# dev_style_sim7000a_cell_rev0_1.net
KiCad netlist of a schematic drawn in EAGLE
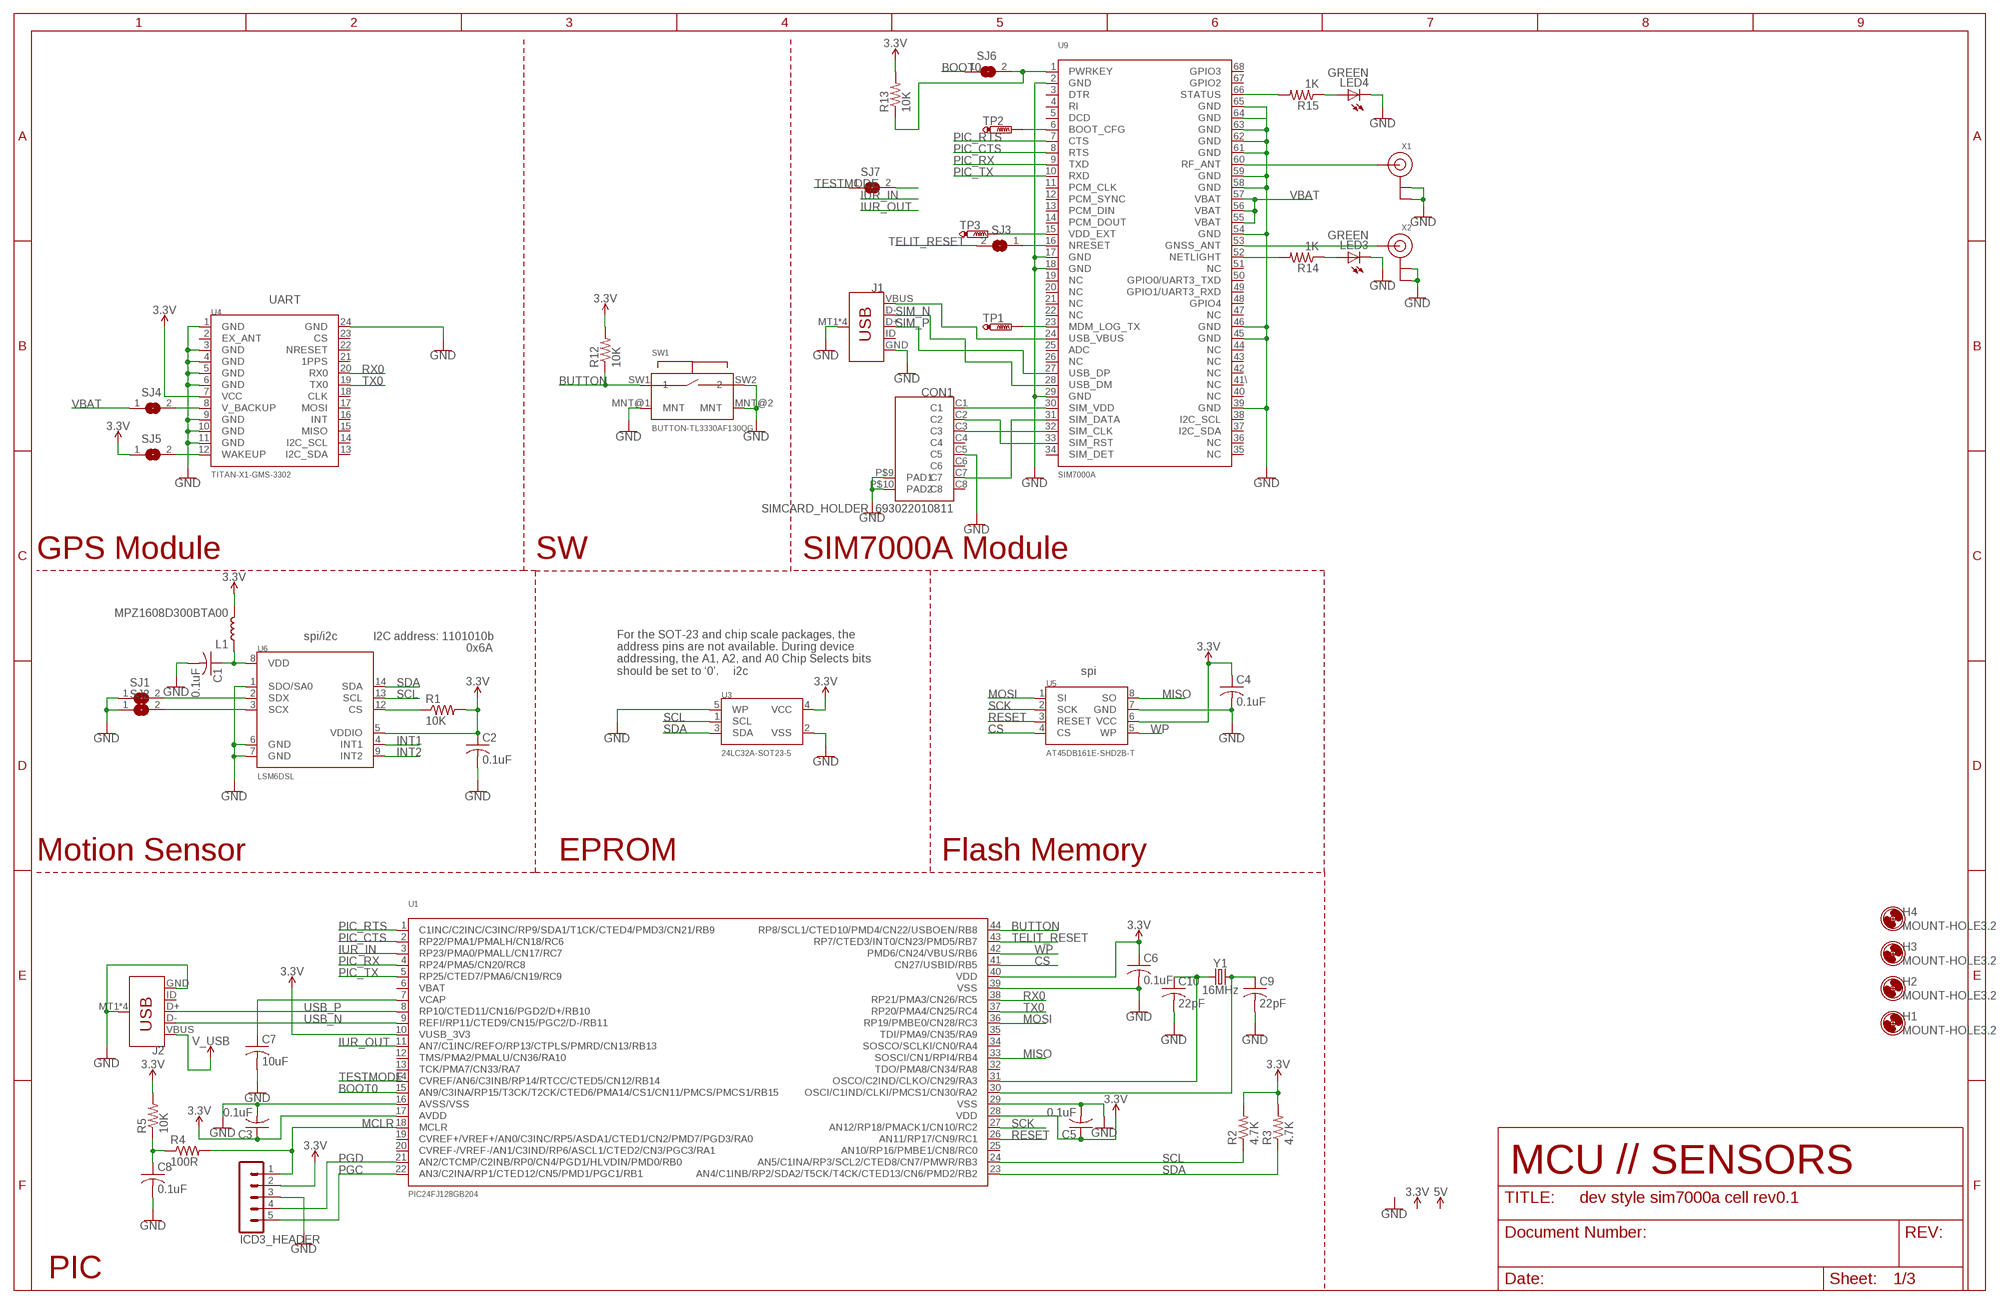
[diagram p0: schematic, sheet 1]
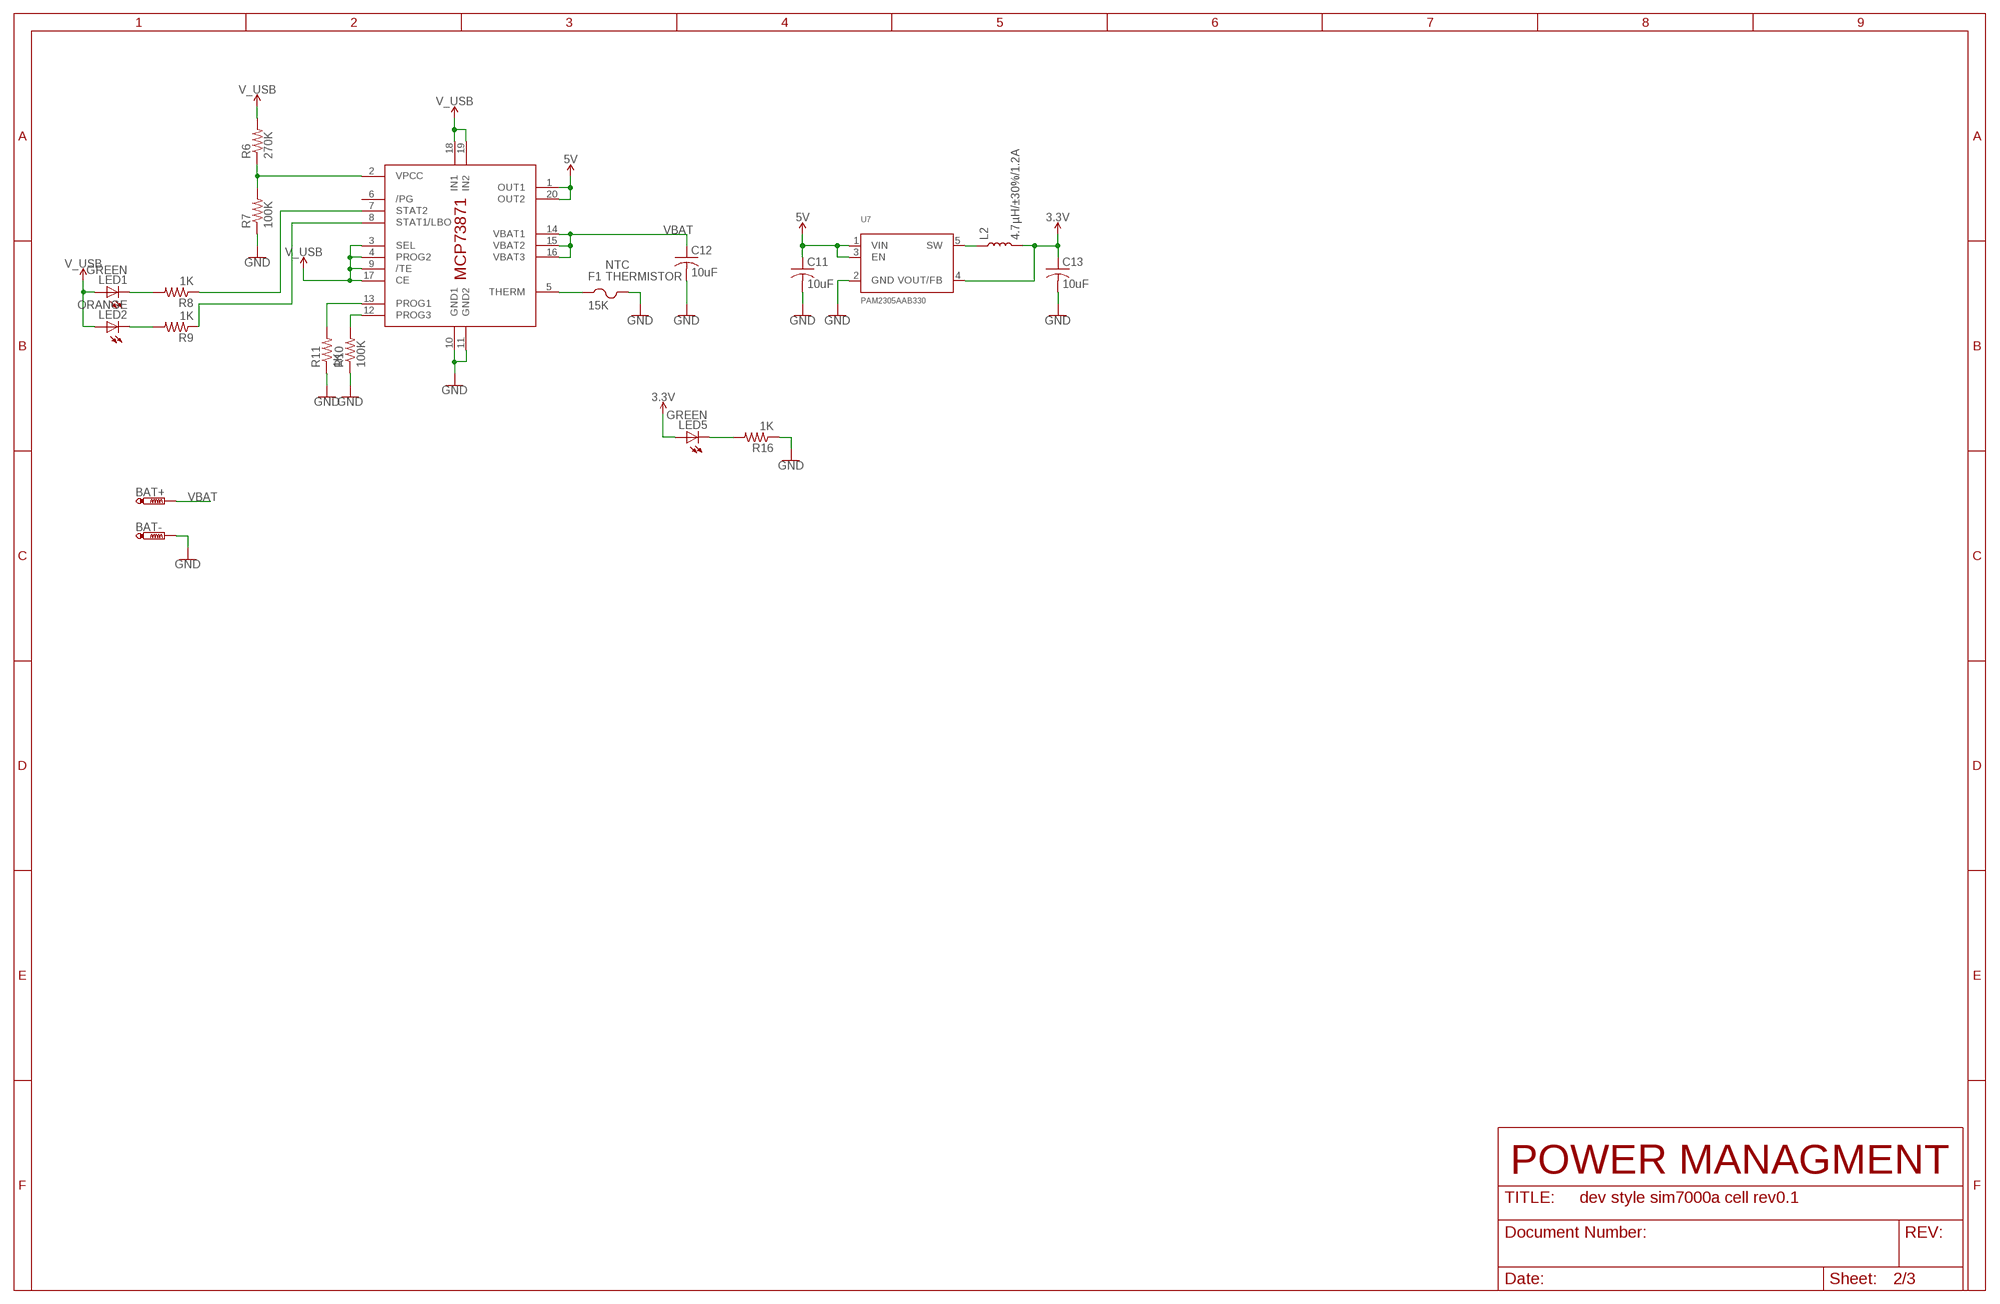
[diagram p1: schematic, sheet 2]
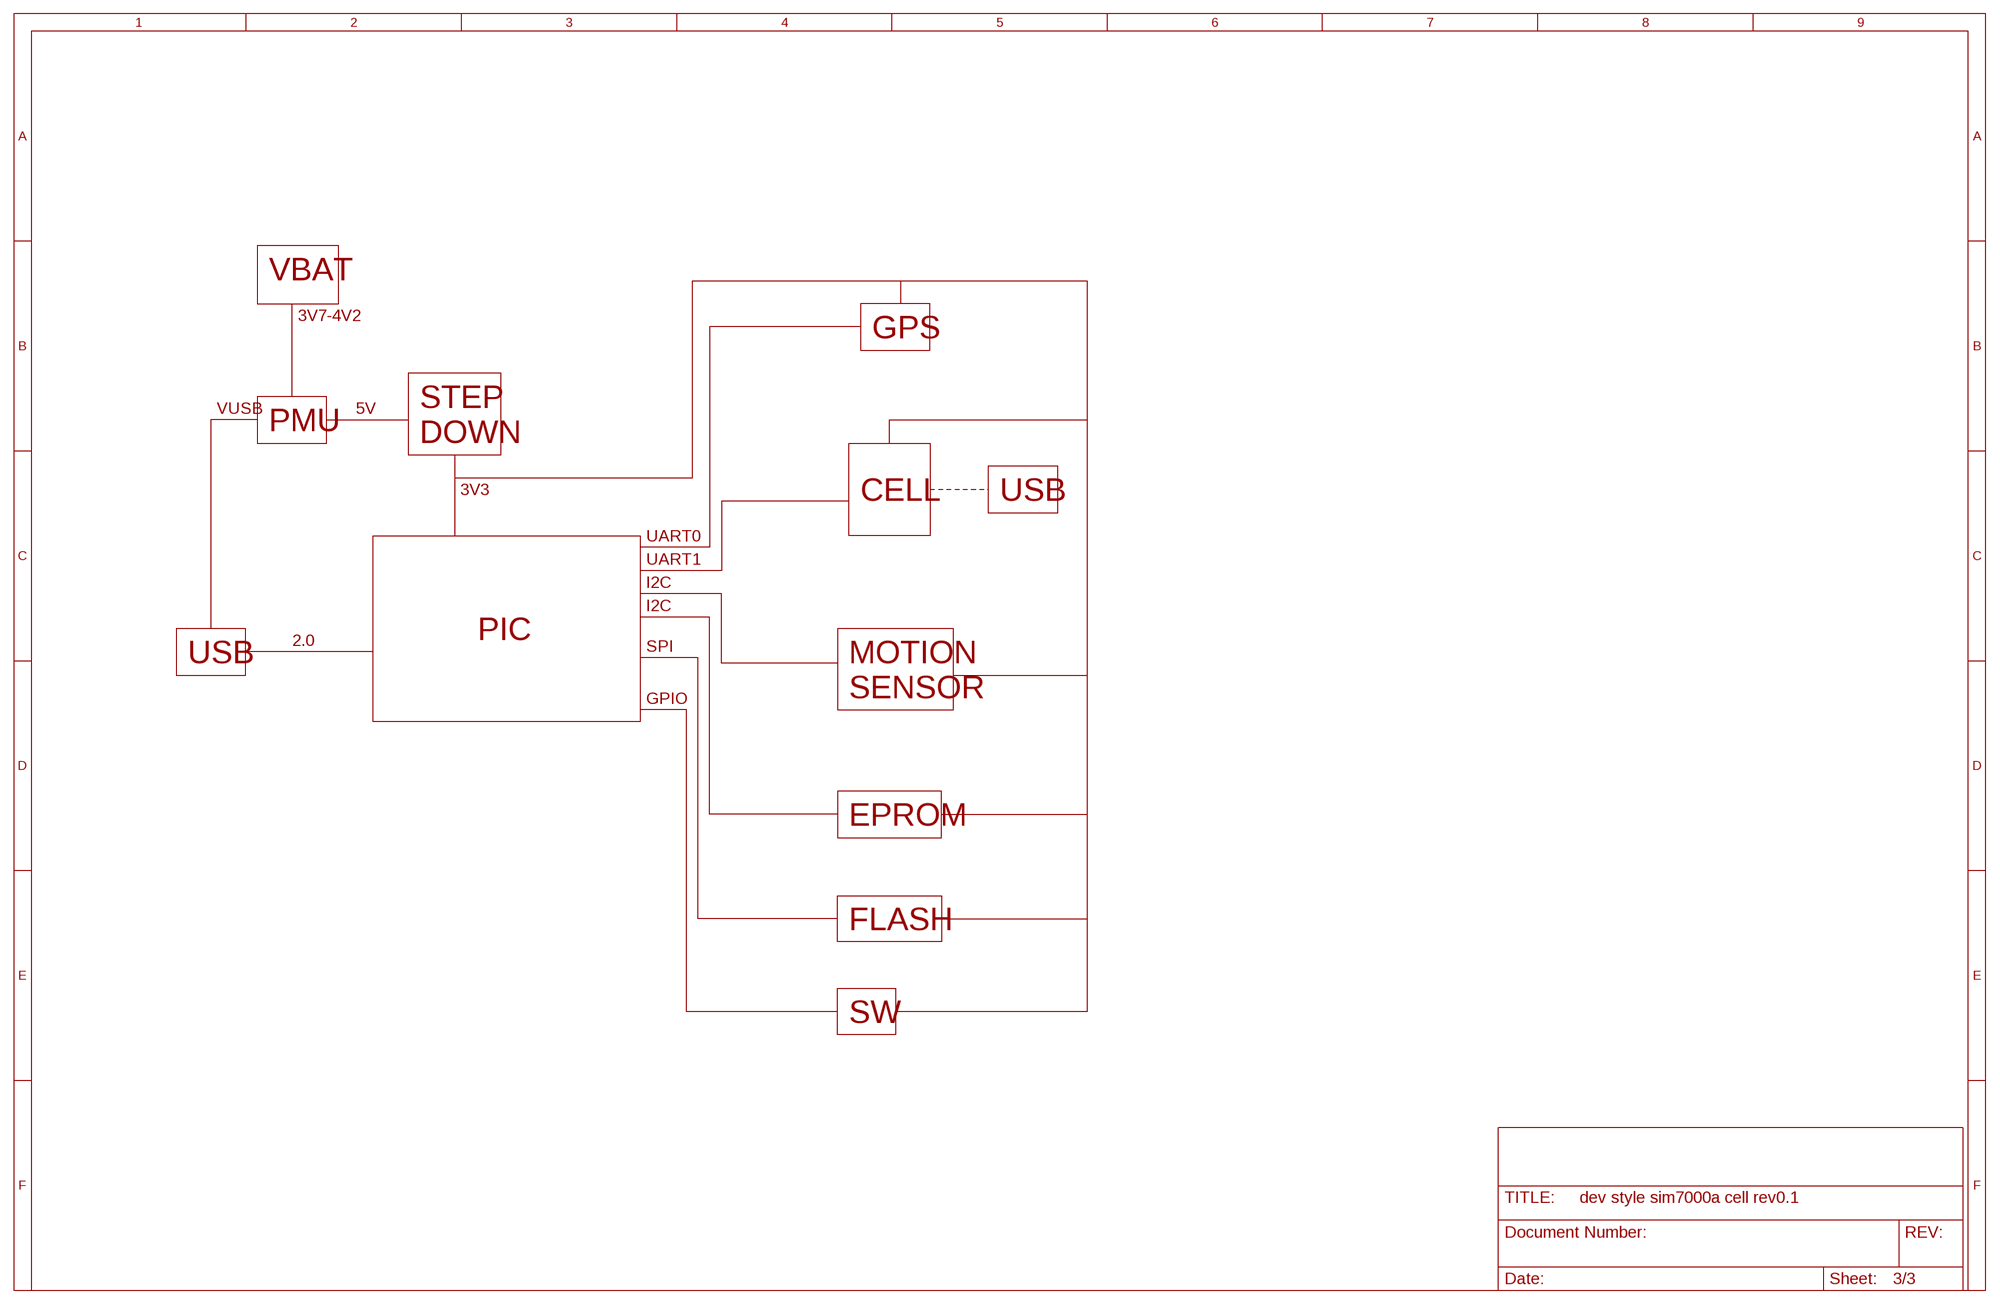
[diagram p2: schematic, sheet 3]

(export (version "E")
  (design (tool "Eeschema 10.0.6"))
  (components
    (comp (ref "C1")
      (value "0.1uF")
      (footprint "eagle-import:C0402")
      (libsource (lib "eagle-import") (part "C-USC0402"))
    )
    (comp (ref "C2")
      (value "0.1uF")
      (footprint "eagle-import:C0402")
      (libsource (lib "eagle-import") (part "C-USC0402"))
    )
    (comp (ref "C3")
      (value "0.1uF")
      (footprint "eagle-import:C0402")
      (libsource (lib "eagle-import") (part "C-USC0402"))
    )
    (comp (ref "C4")
      (value "0.1uF")
      (footprint "eagle-import:C0402")
      (libsource (lib "eagle-import") (part "C-USC0402"))
    )
    (comp (ref "C5")
      (value "0.1uF")
      (footprint "eagle-import:C0402")
      (libsource (lib "eagle-import") (part "C-USC0402"))
    )
    (comp (ref "C6")
      (value "0.1uF")
      (footprint "eagle-import:C0402")
      (libsource (lib "eagle-import") (part "C-USC0402"))
    )
    (comp (ref "C7")
      (value "10uF")
      (footprint "eagle-import:C0603")
      (libsource (lib "eagle-import") (part "C-USC0603"))
    )
    (comp (ref "C8")
      (value "0.1uF")
      (footprint "eagle-import:C0402")
      (libsource (lib "eagle-import") (part "C-USC0402"))
    )
    (comp (ref "C9")
      (value "22pF")
      (footprint "eagle-import:C0402")
      (libsource (lib "eagle-import") (part "C-USC0402"))
    )
    (comp (ref "C10")
      (value "22pF")
      (footprint "eagle-import:C0402")
      (libsource (lib "eagle-import") (part "C-USC0402"))
    )
    (comp (ref "CON1")
      (value "SIMCARD_HOLDER_693022010811")
      (footprint "eagle-import:SIMCARD_HOLDER_693022010811")
      (libsource (lib "eagle-import") (part "SIMCARD_HOLDER_693022010811"))
    )
    (comp (ref "H1")
      (value "MOUNT-HOLE3.2")
      (footprint "eagle-import:3,2")
      (libsource (lib "eagle-import") (part "MOUNT-HOLE3.2"))
    )
    (comp (ref "H2")
      (value "MOUNT-HOLE3.2")
      (footprint "eagle-import:3,2")
      (libsource (lib "eagle-import") (part "MOUNT-HOLE3.2"))
    )
    (comp (ref "H3")
      (value "MOUNT-HOLE3.2")
      (footprint "eagle-import:3,2")
      (libsource (lib "eagle-import") (part "MOUNT-HOLE3.2"))
    )
    (comp (ref "H4")
      (value "MOUNT-HOLE3.2")
      (footprint "eagle-import:3,2")
      (libsource (lib "eagle-import") (part "MOUNT-HOLE3.2"))
    )
    (comp (ref "ICD3_HEADER")
      (value "MA05-1")
      (footprint "eagle-import:MA05-1")
      (libsource (lib "eagle-import") (part "MA05-1"))
    )
    (comp (ref "J1")
      (value "USB_MICRO-B_SMT")
      (footprint "eagle-import:USB-MICROB")
      (libsource (lib "eagle-import") (part "USB_MICRO-B_SMT"))
    )
    (comp (ref "J2")
      (value "USB_MICRO-B_SMT")
      (footprint "eagle-import:USB-MICROB")
      (libsource (lib "eagle-import") (part "USB_MICRO-B_SMT"))
    )
    (comp (ref "L1")
      (value "MPZ1608D300BTA00")
      (footprint "eagle-import:0402")
      (libsource (lib "eagle-import") (part "INDUCTOR-0402-3.9NH"))
    )
    (comp (ref "LED3")
      (value "GREEN")
      (footprint "eagle-import:CHIP-LED0603")
      (libsource (lib "eagle-import") (part "LEDCHIP-LED0603"))
    )
    (comp (ref "LED4")
      (value "GREEN")
      (footprint "eagle-import:CHIP-LED0603")
      (libsource (lib "eagle-import") (part "LEDCHIP-LED0603"))
    )
    (comp (ref "R1")
      (value "10K")
      (footprint "eagle-import:R0402")
      (libsource (lib "eagle-import") (part "R-US_R0402"))
    )
    (comp (ref "R2")
      (value "4.7K")
      (footprint "eagle-import:R0402")
      (libsource (lib "eagle-import") (part "R-US_R0402"))
    )
    (comp (ref "R3")
      (value "4.7K")
      (footprint "eagle-import:R0402")
      (libsource (lib "eagle-import") (part "R-US_R0402"))
    )
    (comp (ref "R4")
      (value "100R")
      (footprint "eagle-import:R0402")
      (libsource (lib "eagle-import") (part "R-US_R0402"))
    )
    (comp (ref "R5")
      (value "10K")
      (footprint "eagle-import:R0402")
      (libsource (lib "eagle-import") (part "R-US_R0402"))
    )
    (comp (ref "R12")
      (value "10K")
      (footprint "eagle-import:R0402")
      (libsource (lib "eagle-import") (part "R-US_R0402"))
    )
    (comp (ref "R13")
      (value "10K")
      (footprint "eagle-import:R0402")
      (libsource (lib "eagle-import") (part "R-US_R0402"))
    )
    (comp (ref "R14")
      (value "1K")
      (footprint "eagle-import:R0402")
      (libsource (lib "eagle-import") (part "R-US_R0402"))
    )
    (comp (ref "R15")
      (value "1K")
      (footprint "eagle-import:R0402")
      (libsource (lib "eagle-import") (part "R-US_R0402"))
    )
    (comp (ref "SJ1") (value "SJ") (footprint "eagle-import:SJ") (libsource (lib "eagle-import") (part "SJ")))
    (comp (ref "SJ2") (value "SJ") (footprint "eagle-import:SJ") (libsource (lib "eagle-import") (part "SJ")))
    (comp (ref "SJ3") (value "SJ") (footprint "eagle-import:SJ") (libsource (lib "eagle-import") (part "SJ")))
    (comp (ref "SJ4") (value "SJ") (footprint "eagle-import:SJ") (libsource (lib "eagle-import") (part "SJ")))
    (comp (ref "SJ5") (value "SJ") (footprint "eagle-import:SJ") (libsource (lib "eagle-import") (part "SJ")))
    (comp (ref "SJ6") (value "SJ") (footprint "eagle-import:SJ") (libsource (lib "eagle-import") (part "SJ")))
    (comp (ref "SJ7") (value "SJ") (footprint "eagle-import:SJ") (libsource (lib "eagle-import") (part "SJ")))
    (comp (ref "SW1")
      (value "BUTTON-TL3330AF130QG")
      (footprint "eagle-import:BUTTON-TL3330AF130QG")
      (libsource (lib "eagle-import") (part "BUTTON-TL3330AF130QG"))
    )
    (comp (ref "TP1")
      (value "PTR1PAD1-17")
      (footprint "eagle-import:P1-17")
      (libsource (lib "eagle-import") (part "PTR1PAD1-17"))
    )
    (comp (ref "TP2")
      (value "PTR1PAD1-17")
      (footprint "eagle-import:P1-17")
      (libsource (lib "eagle-import") (part "PTR1PAD1-17"))
    )
    (comp (ref "TP3")
      (value "PTR1PAD1-17")
      (footprint "eagle-import:P1-17")
      (libsource (lib "eagle-import") (part "PTR1PAD1-17"))
    )
    (comp (ref "U$1")
      (value "FIDUCIAL")
      (footprint "eagle-import:FIDUCIAL_1MM")
      (libsource (lib "eagle-import") (part "FIDUCIAL"))
    )
    (comp (ref "U$2")
      (value "FIDUCIAL")
      (footprint "eagle-import:FIDUCIAL_1MM")
      (libsource (lib "eagle-import") (part "FIDUCIAL"))
    )
    (comp (ref "U$3")
      (value "FIDUCIAL")
      (footprint "eagle-import:FIDUCIAL_1MM")
      (libsource (lib "eagle-import") (part "FIDUCIAL"))
    )
    (comp (ref "U$4")
      (value "FIDUCIAL")
      (footprint "eagle-import:FIDUCIAL_1MM")
      (libsource (lib "eagle-import") (part "FIDUCIAL"))
    )
    (comp (ref "U1")
      (value "PIC24FJ128GB204")
      (footprint "eagle-import:PIC24FJ128GB204")
      (libsource (lib "eagle-import") (part "PIC24FJ128GB204"))
    )
    (comp (ref "U3")
      (value "24LC32A-SOT23-5")
      (footprint "eagle-import:24LC32A-SOT23-5")
      (libsource (lib "eagle-import") (part "24LC32A-SOT23-5"))
    )
    (comp (ref "U4")
      (value "TITAN-X1-GMS-3302")
      (footprint "eagle-import:TITAN-X1-GMS-3302")
      (libsource (lib "eagle-import") (part "TITAN-X1-GMS-3302"))
    )
    (comp (ref "U5")
      (value "AT45DB161E-SHD2B-T")
      (footprint "eagle-import:AT45DB161E-SHD2B-T")
      (libsource (lib "eagle-import") (part "AT45DB161E-SHD2B-T"))
    )
    (comp (ref "U6")
      (value "LSM6DSL")
      (footprint "eagle-import:LSM6DSL")
      (fields (field (name "SPICEPREFIX") "X"))
      (libsource (lib "eagle-import") (part "LSM6DSL"))
    )
    (comp (ref "U9")
      (value "SIM7000A")
      (footprint "eagle-import:SIM7000A")
      (libsource (lib "eagle-import") (part "SIM7000A"))
    )
    (comp (ref "X1")
      (value "ANTENNA_U.FL")
      (footprint "eagle-import:U.FL")
      (libsource (lib "eagle-import") (part "ANTENNA_U.FL"))
    )
    (comp (ref "X2")
      (value "ANTENNA_U.FL")
      (footprint "eagle-import:U.FL")
      (libsource (lib "eagle-import") (part "ANTENNA_U.FL"))
    )
    (comp (ref "Y1")
      (value "16MHz")
      (footprint "eagle-import:CRYSTAL-SMD-5X3.2-4PAD")
      (libsource (lib "eagle-import") (part "CRYSTAL-16MHZSMD-5X3.2"))
    )
    (comp (ref "BAT+")
      (value "PTR1B2,54")
      (footprint "eagle-import:B2,54")
      (libsource (lib "eagle-import") (part "PTR1B2,54"))
    )
    (comp (ref "BAT-")
      (value "PTR1B2,54")
      (footprint "eagle-import:B2,54")
      (libsource (lib "eagle-import") (part "PTR1B2,54"))
    )
    (comp (ref "C11")
      (value "10uF")
      (footprint "eagle-import:C0805")
      (libsource (lib "eagle-import") (part "C-USC0805"))
    )
    (comp (ref "C12")
      (value "10uF")
      (footprint "eagle-import:C0603")
      (libsource (lib "eagle-import") (part "C-USC0603"))
    )
    (comp (ref "C13")
      (value "10uF")
      (footprint "eagle-import:C0805")
      (libsource (lib "eagle-import") (part "C-USC0805"))
    )
    (comp (ref "F1")
      (value "15K")
      (footprint "eagle-import:R1206")
      (libsource (lib "eagle-import") (part "PTCFUSE-1206"))
    )
    (comp (ref "L2")
      (value "4.7µH/±30%/1.2A")
      (footprint "eagle-import:INDUCTOR_4.7UH")
      (libsource (lib "eagle-import") (part "INDUCTOR-CDRH-4.7UH"))
    )
    (comp (ref "LED1")
      (value "GREEN")
      (footprint "eagle-import:CHIP-LED0603")
      (libsource (lib "eagle-import") (part "LEDCHIP-LED0603"))
    )
    (comp (ref "LED2")
      (value "ORANGE")
      (footprint "eagle-import:CHIP-LED0603")
      (libsource (lib "eagle-import") (part "LEDCHIP-LED0603"))
    )
    (comp (ref "LED5")
      (value "GREEN")
      (footprint "eagle-import:CHIP-LED0603")
      (libsource (lib "eagle-import") (part "LEDCHIP-LED0603"))
    )
    (comp (ref "R6")
      (value "270K")
      (footprint "eagle-import:R0402")
      (libsource (lib "eagle-import") (part "R-US_R0402"))
    )
    (comp (ref "R7")
      (value "100K")
      (footprint "eagle-import:R0402")
      (libsource (lib "eagle-import") (part "R-US_R0402"))
    )
    (comp (ref "R8")
      (value "1K")
      (footprint "eagle-import:R0402")
      (libsource (lib "eagle-import") (part "R-US_R0402"))
    )
    (comp (ref "R9")
      (value "1K")
      (footprint "eagle-import:R0402")
      (libsource (lib "eagle-import") (part "R-US_R0402"))
    )
    (comp (ref "R10")
      (value "100K")
      (footprint "eagle-import:R0402")
      (libsource (lib "eagle-import") (part "R-US_R0402"))
    )
    (comp (ref "R11")
      (value "1K")
      (footprint "eagle-import:R0402")
      (libsource (lib "eagle-import") (part "R-US_R0402"))
    )
    (comp (ref "R16")
      (value "1K")
      (footprint "eagle-import:R0402")
      (libsource (lib "eagle-import") (part "R-US_R0402"))
    )
    (comp (ref "U7")
      (value "PAM2305AAB330")
      (footprint "eagle-import:PAM2305AAB330")
      (libsource (lib "eagle-import") (part "PAM2305AAB330"))
    )
    (comp (ref "U8")
      (value "MCP73871")
      (footprint "eagle-import:QFN20")
      (libsource (lib "eagle-import") (part "MCP73871"))
    )
  )
  (nets
    (net (code "1") (name "3.3V") (class "Default")
      (node (ref "C13") (pin "1") (pinfunction "1_1") (pintype "passive"))
      (node (ref "C2") (pin "1") (pinfunction "1_1") (pintype "passive"))
      (node (ref "C3") (pin "1") (pinfunction "1_1") (pintype "passive"))
      (node (ref "C4") (pin "1") (pinfunction "1_1") (pintype "passive"))
      (node (ref "C5") (pin "1") (pinfunction "1_1") (pintype "passive"))
      (node (ref "C6") (pin "1") (pinfunction "1_1") (pintype "passive"))
      (node (ref "ICD3_HEADER") (pin "2") (pinfunction "2_2") (pintype "passive"))
      (node (ref "L1") (pin "2") (pinfunction "2_2") (pintype "passive"))
      (node (ref "L2") (pin "P$2") (pinfunction "2_P$2") (pintype "passive"))
      (node (ref "LED5") (pin "A") (pinfunction "A_A") (pintype "passive"))
      (node (ref "R1") (pin "2") (pinfunction "2_2") (pintype "passive"))
      (node (ref "R12") (pin "2") (pinfunction "2_2") (pintype "passive"))
      (node (ref "R13") (pin "2") (pinfunction "2_2") (pintype "passive"))
      (node (ref "R2") (pin "2") (pinfunction "2_2") (pintype "passive"))
      (node (ref "R3") (pin "2") (pinfunction "2_2") (pintype "passive"))
      (node (ref "R5") (pin "2") (pinfunction "2_2") (pintype "passive"))
      (node (ref "SJ5") (pin "1") (pinfunction "1_1") (pintype "passive"))
      (node (ref "U1") (pin "10") (pinfunction "VUSB_3V3_10") (pintype "bidirectional"))
      (node (ref "U1") (pin "17") (pinfunction "AVDD_17") (pintype "bidirectional"))
      (node (ref "U1") (pin "28") (pinfunction "VDD_28") (pintype "bidirectional"))
      (node (ref "U1") (pin "40") (pinfunction "VDD_40") (pintype "bidirectional"))
      (node (ref "U3") (pin "4") (pinfunction "VCC_4") (pintype "bidirectional"))
      (node (ref "U4") (pin "7") (pinfunction "VCC_7") (pintype "bidirectional"))
      (node (ref "U5") (pin "6") (pinfunction "VCC_6") (pintype "bidirectional"))
      (node (ref "U6") (pin "5") (pinfunction "VDDIO_5") (pintype "bidirectional"))
      (node (ref "U7") (pin "4") (pinfunction "VOUT/FB_4") (pintype "bidirectional"))
    )
    (net (code "2") (name "5V") (class "Default")
      (node (ref "C11") (pin "1") (pinfunction "1_1") (pintype "passive"))
      (node (ref "U7") (pin "1") (pinfunction "VIN_1") (pintype "bidirectional"))
      (node (ref "U7") (pin "3") (pinfunction "EN_3") (pintype "bidirectional"))
      (node (ref "U8") (pin "1") (pinfunction "OUT1_1") (pintype "output"))
      (node (ref "U8") (pin "20") (pinfunction "OUT2_20") (pintype "output"))
    )
    (net (code "3") (name "BOOT0") (class "Default")
      (node (ref "SJ6") (pin "1") (pinfunction "1_1") (pintype "passive"))
      (node (ref "U1") (pin "15") (pinfunction "AN9/C3INA/RP15/T3CK/T2CK/CTED6/PMA14/CS1/CN11/PMCS/PMCS1/RB15_15") (pintype "bidirectional"))
    )
    (net (code "4") (name "BUTTON") (class "Default")
      (node (ref "R12") (pin "1") (pinfunction "1_1") (pintype "passive"))
      (node (ref "SW1") (pin "SW1") (pinfunction "1_SW1") (pintype "bidirectional"))
      (node (ref "U1") (pin "44") (pinfunction "RP8/SCL1/CTED10/PMD4/CN22/USBOEN/RB8_44") (pintype "bidirectional"))
    )
    (net (code "5") (name "CS") (class "Default")
      (node (ref "U1") (pin "41") (pinfunction "CN27/USBID/RB5_41") (pintype "bidirectional"))
      (node (ref "U5") (pin "4") (pinfunction "CS_4") (pintype "bidirectional"))
    )
    (net (code "6") (name "GND") (class "Default")
      (node (ref "BAT-") (pin "TP") (pinfunction "TP_TP") (pintype "input"))
      (node (ref "C1") (pin "2") (pinfunction "2_2") (pintype "passive"))
      (node (ref "C10") (pin "2") (pinfunction "2_2") (pintype "passive"))
      (node (ref "C11") (pin "2") (pinfunction "2_2") (pintype "passive"))
      (node (ref "C12") (pin "2") (pinfunction "2_2") (pintype "passive"))
      (node (ref "C13") (pin "2") (pinfunction "2_2") (pintype "passive"))
      (node (ref "C2") (pin "2") (pinfunction "2_2") (pintype "passive"))
      (node (ref "C3") (pin "2") (pinfunction "2_2") (pintype "passive"))
      (node (ref "C4") (pin "2") (pinfunction "2_2") (pintype "passive"))
      (node (ref "C5") (pin "2") (pinfunction "2_2") (pintype "passive"))
      (node (ref "C6") (pin "2") (pinfunction "2_2") (pintype "passive"))
      (node (ref "C7") (pin "2") (pinfunction "2_2") (pintype "passive"))
      (node (ref "C8") (pin "2") (pinfunction "2_2") (pintype "passive"))
      (node (ref "C9") (pin "2") (pinfunction "2_2") (pintype "passive"))
      (node (ref "CON1") (pin "C5") (pinfunction "C5_C5") (pintype "bidirectional"))
      (node (ref "CON1") (pin "P$10") (pinfunction "PAD2_P$10") (pintype "bidirectional"))
      (node (ref "CON1") (pin "P$9") (pinfunction "PAD1_P$9") (pintype "bidirectional"))
      (node (ref "F1") (pin "2") (pinfunction "2_2") (pintype "passive"))
      (node (ref "ICD3_HEADER") (pin "3") (pinfunction "3_3") (pintype "passive"))
      (node (ref "J1") (pin "GND") (pinfunction "GND_GND") (pintype "power_in"))
      (node (ref "J1") (pin "MT1") (pinfunction "SHIELD_MT1") (pintype "bidirectional"))
      (node (ref "J1") (pin "MT2") (pinfunction "SHIELD_MT2") (pintype "bidirectional"))
      (node (ref "J1") (pin "P$1") (pinfunction "SHIELD_P$1") (pintype "bidirectional"))
      (node (ref "J1") (pin "P$2") (pinfunction "SHIELD_P$2") (pintype "bidirectional"))
      (node (ref "J2") (pin "GND") (pinfunction "GND_GND") (pintype "power_in"))
      (node (ref "J2") (pin "MT1") (pinfunction "SHIELD_MT1") (pintype "bidirectional"))
      (node (ref "J2") (pin "MT2") (pinfunction "SHIELD_MT2") (pintype "bidirectional"))
      (node (ref "J2") (pin "P$1") (pinfunction "SHIELD_P$1") (pintype "bidirectional"))
      (node (ref "J2") (pin "P$2") (pinfunction "SHIELD_P$2") (pintype "bidirectional"))
      (node (ref "LED3") (pin "C") (pinfunction "C_C") (pintype "passive"))
      (node (ref "LED4") (pin "C") (pinfunction "C_C") (pintype "passive"))
      (node (ref "R10") (pin "1") (pinfunction "1_1") (pintype "passive"))
      (node (ref "R11") (pin "1") (pinfunction "1_1") (pintype "passive"))
      (node (ref "R16") (pin "1") (pinfunction "1_1") (pintype "passive"))
      (node (ref "R7") (pin "1") (pinfunction "1_1") (pintype "passive"))
      (node (ref "SJ1") (pin "1") (pinfunction "1_1") (pintype "passive"))
      (node (ref "SJ2") (pin "1") (pinfunction "1_1") (pintype "passive"))
      (node (ref "SW1") (pin "MNT@1") (pinfunction "MNT_MNT@1") (pintype "bidirectional"))
      (node (ref "SW1") (pin "MNT@2") (pinfunction "MNT_MNT@2") (pintype "bidirectional"))
      (node (ref "SW1") (pin "SW2") (pinfunction "2_SW2") (pintype "bidirectional"))
      (node (ref "U1") (pin "16") (pinfunction "AVSS/VSS_16") (pintype "bidirectional"))
      (node (ref "U1") (pin "29") (pinfunction "VSS_29") (pintype "bidirectional"))
      (node (ref "U1") (pin "39") (pinfunction "VSS_39") (pintype "bidirectional"))
      (node (ref "U3") (pin "2") (pinfunction "VSS_2") (pintype "bidirectional"))
      (node (ref "U3") (pin "5") (pinfunction "WP_5") (pintype "bidirectional"))
      (node (ref "U4") (pin "1") (pinfunction "GND_1") (pintype "bidirectional"))
      (node (ref "U4") (pin "10") (pinfunction "GND_10") (pintype "bidirectional"))
      (node (ref "U4") (pin "11") (pinfunction "GND_11") (pintype "bidirectional"))
      (node (ref "U4") (pin "24") (pinfunction "GND_24") (pintype "bidirectional"))
      (node (ref "U4") (pin "3") (pinfunction "GND_3") (pintype "bidirectional"))
      (node (ref "U4") (pin "4") (pinfunction "GND_4") (pintype "bidirectional"))
      (node (ref "U4") (pin "5") (pinfunction "GND_5") (pintype "bidirectional"))
      (node (ref "U4") (pin "6") (pinfunction "GND_6") (pintype "bidirectional"))
      (node (ref "U4") (pin "9") (pinfunction "GND_9") (pintype "bidirectional"))
      (node (ref "U5") (pin "7") (pinfunction "GND_7") (pintype "bidirectional"))
      (node (ref "U6") (pin "1") (pinfunction "SDO/SA0_1") (pintype "bidirectional"))
      (node (ref "U6") (pin "6") (pinfunction "GND_6") (pintype "bidirectional"))
      (node (ref "U6") (pin "7") (pinfunction "GND_7") (pintype "bidirectional"))
      (node (ref "U7") (pin "2") (pinfunction "GND_2") (pintype "bidirectional"))
      (node (ref "U8") (pin "10") (pinfunction "GND1_10") (pintype "power_in"))
      (node (ref "U8") (pin "11") (pinfunction "GND2_11") (pintype "power_in"))
      (node (ref "U9") (pin "17") (pinfunction "GND_17") (pintype "power_in"))
      (node (ref "U9") (pin "18") (pinfunction "GND_18") (pintype "power_in"))
      (node (ref "U9") (pin "2") (pinfunction "GND_2") (pintype "power_in"))
      (node (ref "U9") (pin "29") (pinfunction "GND_29") (pintype "power_in"))
      (node (ref "U9") (pin "39") (pinfunction "GND_39") (pintype "power_in"))
      (node (ref "U9") (pin "45") (pinfunction "GND_45") (pintype "power_in"))
      (node (ref "U9") (pin "46") (pinfunction "GND_46") (pintype "power_in"))
      (node (ref "U9") (pin "54") (pinfunction "GND_54") (pintype "power_in"))
      (node (ref "U9") (pin "58") (pinfunction "GND_58") (pintype "power_in"))
      (node (ref "U9") (pin "59") (pinfunction "GND_59") (pintype "power_in"))
      (node (ref "U9") (pin "61") (pinfunction "GND_61") (pintype "power_in"))
      (node (ref "U9") (pin "62") (pinfunction "GND_62") (pintype "power_in"))
      (node (ref "U9") (pin "63") (pinfunction "GND_63") (pintype "power_in"))
      (node (ref "U9") (pin "64") (pinfunction "GND_64") (pintype "power_in"))
      (node (ref "U9") (pin "65") (pinfunction "GND_65") (pintype "power_in"))
      (node (ref "X1") (pin "1") (pinfunction "GND_1") (pintype "passive"))
      (node (ref "X1") (pin "2") (pinfunction "GND_2") (pintype "passive"))
      (node (ref "X2") (pin "1") (pinfunction "GND_1") (pintype "passive"))
      (node (ref "X2") (pin "2") (pinfunction "GND_2") (pintype "passive"))
    )
    (net (code "7") (name "INT1") (class "Default")
      (node (ref "U6") (pin "4") (pinfunction "INT1_4") (pintype "bidirectional"))
    )
    (net (code "8") (name "INT2") (class "Default")
      (node (ref "U6") (pin "9") (pinfunction "INT2_9") (pintype "bidirectional"))
    )
    (net (code "9") (name "IUR_IN") (class "Default")
      (node (ref "U1") (pin "3") (pinfunction "RP23/PMA0/PMALL/CN17/RC7_3") (pintype "bidirectional"))
    )
    (net (code "10") (name "IUR_OUT") (class "Default")
      (node (ref "U1") (pin "11") (pinfunction "AN7/C1INC/REFO/RP13/CTPLS/PMRD/CN13/RB13_11") (pintype "bidirectional"))
    )
    (net (code "11") (name "MCLR") (class "Default")
      (node (ref "ICD3_HEADER") (pin "1") (pinfunction "1_1") (pintype "passive"))
      (node (ref "R4") (pin "2") (pinfunction "2_2") (pintype "passive"))
      (node (ref "U1") (pin "18") (pinfunction "MCLR_18") (pintype "bidirectional"))
    )
    (net (code "12") (name "MISO") (class "Default")
      (node (ref "U1") (pin "33") (pinfunction "SOSCI/CN1/RPI4/RB4_33") (pintype "bidirectional"))
      (node (ref "U5") (pin "8") (pinfunction "SO_8") (pintype "bidirectional"))
    )
    (net (code "13") (name "MOSI") (class "Default")
      (node (ref "U1") (pin "36") (pinfunction "RP19/PMBE0/CN28/RC3_36") (pintype "bidirectional"))
      (node (ref "U5") (pin "1") (pinfunction "SI_1") (pintype "bidirectional"))
    )
    (net (code "14") (name "Net-(C8-Pad1)") (class "Default")
      (node (ref "C8") (pin "1") (pinfunction "1_1") (pintype "passive"))
      (node (ref "R4") (pin "1") (pinfunction "1_1") (pintype "passive"))
      (node (ref "R5") (pin "1") (pinfunction "1_1") (pintype "passive"))
    )
    (net (code "15") (name "Net-(L2-1)") (class "Default")
      (node (ref "L2") (pin "P$1") (pinfunction "1_P$1") (pintype "passive"))
      (node (ref "U7") (pin "5") (pinfunction "SW_5") (pintype "bidirectional"))
    )
    (net (code "16") (name "Net-(LED1-PadC)") (class "Default")
      (node (ref "LED1") (pin "C") (pinfunction "C_C") (pintype "passive"))
      (node (ref "R8") (pin "2") (pinfunction "2_2") (pintype "passive"))
    )
    (net (code "17") (name "Net-(LED2-PadC)") (class "Default")
      (node (ref "LED2") (pin "C") (pinfunction "C_C") (pintype "passive"))
      (node (ref "R9") (pin "2") (pinfunction "2_2") (pintype "passive"))
    )
    (net (code "18") (name "Net-(LED3-PadA)") (class "Default")
      (node (ref "LED3") (pin "A") (pinfunction "A_A") (pintype "passive"))
      (node (ref "R14") (pin "1") (pinfunction "1_1") (pintype "passive"))
    )
    (net (code "19") (name "Net-(LED4-PadA)") (class "Default")
      (node (ref "LED4") (pin "A") (pinfunction "A_A") (pintype "passive"))
      (node (ref "R15") (pin "1") (pinfunction "1_1") (pintype "passive"))
    )
    (net (code "20") (name "Net-(LED5-PadC)") (class "Default")
      (node (ref "LED5") (pin "C") (pinfunction "C_C") (pintype "passive"))
      (node (ref "R16") (pin "2") (pinfunction "2_2") (pintype "passive"))
    )
    (net (code "21") (name "Net-(U1-OSCI{slash}C1IND{slash}CLKI{slash}PMCS1{slash}CN30{slash}RA2)") (class "Default")
      (node (ref "C9") (pin "1") (pinfunction "1_1") (pintype "passive"))
      (node (ref "U1") (pin "30") (pinfunction "OSCI/C1IND/CLKI/PMCS1/CN30/RA2_30") (pintype "bidirectional"))
      (node (ref "Y1") (pin "3") (pinfunction "2_3") (pintype "passive"))
    )
    (net (code "22") (name "Net-(U1-OSCO{slash}C2IND{slash}CLKO{slash}CN29{slash}RA3)") (class "Default")
      (node (ref "C10") (pin "1") (pinfunction "1_1") (pintype "passive"))
      (node (ref "U1") (pin "31") (pinfunction "OSCO/C2IND/CLKO/CN29/RA3_31") (pintype "bidirectional"))
      (node (ref "Y1") (pin "1") (pinfunction "1_1") (pintype "passive"))
    )
    (net (code "23") (name "Net-(U1-VCAP)") (class "Default")
      (node (ref "C7") (pin "1") (pinfunction "1_1") (pintype "passive"))
      (node (ref "U1") (pin "7") (pinfunction "VCAP_7") (pintype "bidirectional"))
    )
    (net (code "24") (name "Net-(U4-V_BACKUP)") (class "Default")
      (node (ref "SJ4") (pin "2") (pinfunction "2_2") (pintype "passive"))
      (node (ref "U4") (pin "8") (pinfunction "V_BACKUP_8") (pintype "bidirectional"))
    )
    (net (code "25") (name "Net-(U4-WAKEUP)") (class "Default")
      (node (ref "SJ5") (pin "2") (pinfunction "2_2") (pintype "passive"))
      (node (ref "U4") (pin "12") (pinfunction "WAKEUP_12") (pintype "bidirectional"))
    )
    (net (code "26") (name "Net-(U6-CS)") (class "Default")
      (node (ref "R1") (pin "1") (pinfunction "1_1") (pintype "passive"))
      (node (ref "U6") (pin "12") (pinfunction "CS_12") (pintype "bidirectional"))
    )
    (net (code "27") (name "Net-(U6-SCX)") (class "Default")
      (node (ref "SJ2") (pin "2") (pinfunction "2_2") (pintype "passive"))
      (node (ref "U6") (pin "3") (pinfunction "SCX_3") (pintype "bidirectional"))
    )
    (net (code "28") (name "Net-(U6-SDX)") (class "Default")
      (node (ref "SJ1") (pin "2") (pinfunction "2_2") (pintype "passive"))
      (node (ref "U6") (pin "2") (pinfunction "SDX_2") (pintype "bidirectional"))
    )
    (net (code "29") (name "Net-(U6-VDD)") (class "Default")
      (node (ref "C1") (pin "1") (pinfunction "1_1") (pintype "passive"))
      (node (ref "L1") (pin "1") (pinfunction "1_1") (pintype "passive"))
      (node (ref "U6") (pin "8") (pinfunction "VDD_8") (pintype "bidirectional"))
    )
    (net (code "30") (name "Net-(U8-PROG1)") (class "Default")
      (node (ref "R11") (pin "2") (pinfunction "2_2") (pintype "passive"))
      (node (ref "U8") (pin "13") (pinfunction "PROG1_13") (pintype "input"))
    )
    (net (code "31") (name "Net-(U8-PROG3)") (class "Default")
      (node (ref "R10") (pin "2") (pinfunction "2_2") (pintype "passive"))
      (node (ref "U8") (pin "12") (pinfunction "PROG3_12") (pintype "input"))
    )
    (net (code "32") (name "Net-(U8-STAT1{slash}LBO)") (class "Default")
      (node (ref "R9") (pin "1") (pinfunction "1_1") (pintype "passive"))
      (node (ref "U8") (pin "8") (pinfunction "STAT1/LBO_8") (pintype "output"))
    )
    (net (code "33") (name "Net-(U8-STAT2)") (class "Default")
      (node (ref "R8") (pin "1") (pinfunction "1_1") (pintype "passive"))
      (node (ref "U8") (pin "7") (pinfunction "STAT2_7") (pintype "output"))
    )
    (net (code "34") (name "Net-(U8-THERM)") (class "Default")
      (node (ref "F1") (pin "1") (pinfunction "1_1") (pintype "passive"))
      (node (ref "U8") (pin "5") (pinfunction "THERM_5") (pintype "input"))
    )
    (net (code "35") (name "Net-(U8-VPCC)") (class "Default")
      (node (ref "R6") (pin "1") (pinfunction "1_1") (pintype "passive"))
      (node (ref "R7") (pin "2") (pinfunction "2_2") (pintype "passive"))
      (node (ref "U8") (pin "2") (pinfunction "VPCC_2") (pintype "input"))
    )
    (net (code "36") (name "Net-(U9-BOOT_CFG)") (class "Default")
      (node (ref "TP2") (pin "TP") (pinfunction "TP_TP") (pintype "input"))
      (node (ref "U9") (pin "6") (pinfunction "BOOT_CFG_6") (pintype "bidirectional"))
    )
    (net (code "37") (name "Net-(U9-GNSS_ANT)") (class "Default")
      (node (ref "U9") (pin "53") (pinfunction "GNSS_ANT_53") (pintype "bidirectional"))
      (node (ref "X2") (pin "3") (pinfunction "SIGNAL_3") (pintype "passive"))
    )
    (net (code "38") (name "Net-(U9-MDM_LOG_TX)") (class "Default")
      (node (ref "TP1") (pin "TP") (pinfunction "TP_TP") (pintype "input"))
      (node (ref "U9") (pin "23") (pinfunction "MDM_LOG_TX_23") (pintype "bidirectional"))
    )
    (net (code "39") (name "Net-(U9-NETLIGHT)") (class "Default")
      (node (ref "R14") (pin "2") (pinfunction "2_2") (pintype "passive"))
      (node (ref "U9") (pin "52") (pinfunction "NETLIGHT_52") (pintype "bidirectional"))
    )
    (net (code "40") (name "Net-(U9-NRESET)") (class "Default")
      (node (ref "SJ3") (pin "1") (pinfunction "1_1") (pintype "passive"))
      (node (ref "U9") (pin "16") (pinfunction "NRESET_16") (pintype "bidirectional"))
    )
    (net (code "41") (name "Net-(U9-PWRKEY)") (class "Default")
      (node (ref "R13") (pin "1") (pinfunction "1_1") (pintype "passive"))
      (node (ref "SJ6") (pin "2") (pinfunction "2_2") (pintype "passive"))
      (node (ref "U9") (pin "1") (pinfunction "PWRKEY_1") (pintype "bidirectional"))
    )
    (net (code "42") (name "Net-(U9-RF_ANT)") (class "Default")
      (node (ref "U9") (pin "60") (pinfunction "RF_ANT_60") (pintype "bidirectional"))
      (node (ref "X1") (pin "3") (pinfunction "SIGNAL_3") (pintype "passive"))
    )
    (net (code "43") (name "Net-(U9-SIM_CLK)") (class "Default")
      (node (ref "CON1") (pin "C3") (pinfunction "C3_C3") (pintype "bidirectional"))
      (node (ref "U9") (pin "32") (pinfunction "SIM_CLK_32") (pintype "bidirectional"))
    )
    (net (code "44") (name "Net-(U9-SIM_DATA)") (class "Default")
      (node (ref "CON1") (pin "C7") (pinfunction "C7_C7") (pintype "bidirectional"))
      (node (ref "U9") (pin "31") (pinfunction "SIM_DATA_31") (pintype "bidirectional"))
    )
    (net (code "45") (name "Net-(U9-SIM_RST)") (class "Default")
      (node (ref "CON1") (pin "C2") (pinfunction "C2_C2") (pintype "bidirectional"))
      (node (ref "U9") (pin "33") (pinfunction "SIM_RST_33") (pintype "bidirectional"))
    )
    (net (code "46") (name "Net-(U9-SIM_VDD)") (class "Default")
      (node (ref "CON1") (pin "C1") (pinfunction "C1_C1") (pintype "bidirectional"))
      (node (ref "U9") (pin "30") (pinfunction "SIM_VDD_30") (pintype "bidirectional"))
    )
    (net (code "47") (name "Net-(U9-STATUS)") (class "Default")
      (node (ref "R15") (pin "2") (pinfunction "2_2") (pintype "passive"))
      (node (ref "U9") (pin "66") (pinfunction "STATUS_66") (pintype "bidirectional"))
    )
    (net (code "48") (name "Net-(U9-USB_VBUS)") (class "Default")
      (node (ref "J1") (pin "VBUS") (pinfunction "VBUS_VBUS") (pintype "power_in"))
      (node (ref "U9") (pin "24") (pinfunction "USB_VBUS_24") (pintype "power_in"))
    )
    (net (code "49") (name "Net-(U9-VDD_EXT)") (class "Default")
      (node (ref "TP3") (pin "TP") (pinfunction "TP_TP") (pintype "input"))
      (node (ref "U9") (pin "15") (pinfunction "VDD_EXT_15") (pintype "power_in"))
    )
    (net (code "50") (name "PGC") (class "Default")
      (node (ref "ICD3_HEADER") (pin "5") (pinfunction "5_5") (pintype "passive"))
      (node (ref "U1") (pin "22") (pinfunction "AN3/C2INA/RP1/CTED12/CN5/PMD1/PGC1/RB1_22") (pintype "bidirectional"))
    )
    (net (code "51") (name "PGD") (class "Default")
      (node (ref "ICD3_HEADER") (pin "4") (pinfunction "4_4") (pintype "passive"))
      (node (ref "U1") (pin "21") (pinfunction "AN2/CTCMP/C2INB/RP0/CN4/PGD1/HLVDIN/PMD0/RB0_21") (pintype "bidirectional"))
    )
    (net (code "52") (name "PIC_CTS") (class "Default")
      (node (ref "U1") (pin "2") (pinfunction "RP22/PMA1/PMALH/CN18/RC6_2") (pintype "bidirectional"))
      (node (ref "U9") (pin "8") (pinfunction "RTS_8") (pintype "bidirectional"))
    )
    (net (code "53") (name "PIC_RTS") (class "Default")
      (node (ref "U1") (pin "1") (pinfunction "C1INC/C2INC/C3INC/RP9/SDA1/T1CK/CTED4/PMD3/CN21/RB9_1") (pintype "bidirectional"))
      (node (ref "U9") (pin "7") (pinfunction "CTS_7") (pintype "bidirectional"))
    )
    (net (code "54") (name "PIC_RX") (class "Default")
      (node (ref "U1") (pin "4") (pinfunction "RP24/PMA5/CN20/RC8_4") (pintype "bidirectional"))
      (node (ref "U9") (pin "9") (pinfunction "TXD_9") (pintype "bidirectional"))
    )
    (net (code "55") (name "PIC_TX") (class "Default")
      (node (ref "U1") (pin "5") (pinfunction "RP25/CTED7/PMA6/CN19/RC9_5") (pintype "bidirectional"))
      (node (ref "U9") (pin "10") (pinfunction "RXD_10") (pintype "bidirectional"))
    )
    (net (code "56") (name "RESET") (class "Default")
      (node (ref "U1") (pin "26") (pinfunction "AN11/RP17/CN9/RC1_26") (pintype "bidirectional"))
      (node (ref "U5") (pin "3") (pinfunction "RESET_3") (pintype "bidirectional"))
    )
    (net (code "57") (name "RX0") (class "Default")
      (node (ref "U1") (pin "38") (pinfunction "RP21/PMA3/CN26/RC5_38") (pintype "bidirectional"))
      (node (ref "U4") (pin "20") (pinfunction "RX0_20") (pintype "bidirectional"))
    )
    (net (code "58") (name "SCK") (class "Default")
      (node (ref "U1") (pin "27") (pinfunction "AN12/RP18/PMACK1/CN10/RC2_27") (pintype "bidirectional"))
      (node (ref "U5") (pin "2") (pinfunction "SCK_2") (pintype "bidirectional"))
    )
    (net (code "59") (name "SCL") (class "Default")
      (node (ref "R2") (pin "1") (pinfunction "1_1") (pintype "passive"))
      (node (ref "U1") (pin "24") (pinfunction "AN5/C1INA/RP3/SCL2/CTED8/CN7/PMWR/RB3_24") (pintype "bidirectional"))
      (node (ref "U3") (pin "1") (pinfunction "SCL_1") (pintype "bidirectional"))
      (node (ref "U6") (pin "13") (pinfunction "SCL_13") (pintype "bidirectional"))
    )
    (net (code "60") (name "SDA") (class "Default")
      (node (ref "R3") (pin "1") (pinfunction "1_1") (pintype "passive"))
      (node (ref "U1") (pin "23") (pinfunction "AN4/C1INB/RP2/SDA2/T5CK/T4CK/CTED13/CN6/PMD2/RB2_23") (pintype "bidirectional"))
      (node (ref "U3") (pin "3") (pinfunction "SDA_3") (pintype "bidirectional"))
      (node (ref "U6") (pin "14") (pinfunction "SDA_14") (pintype "bidirectional"))
    )
    (net (code "61") (name "SIM_N") (class "Default")
      (node (ref "J1") (pin "D-") (pinfunction "D-_D-") (pintype "bidirectional"))
      (node (ref "U9") (pin "28") (pinfunction "USB_DM_28") (pintype "bidirectional"))
    )
    (net (code "62") (name "SIM_P") (class "Default")
      (node (ref "J1") (pin "D+") (pinfunction "D+_D+") (pintype "bidirectional"))
      (node (ref "U9") (pin "27") (pinfunction "USB_DP_27") (pintype "bidirectional"))
    )
    (net (code "63") (name "TELIT_RESET") (class "Default")
      (node (ref "SJ3") (pin "2") (pinfunction "2_2") (pintype "passive"))
      (node (ref "U1") (pin "43") (pinfunction "RP7/CTED3/INT0/CN23/PMD5/RB7_43") (pintype "bidirectional"))
    )
    (net (code "64") (name "TESTMODE") (class "Default")
      (node (ref "SJ7") (pin "1") (pinfunction "1_1") (pintype "passive"))
      (node (ref "U1") (pin "14") (pinfunction "CVREF/AN6/C3INB/RP14/RTCC/CTED5/CN12/RB14_14") (pintype "bidirectional"))
    )
    (net (code "65") (name "TX0") (class "Default")
      (node (ref "U1") (pin "37") (pinfunction "RP20/PMA4/CN25/RC4_37") (pintype "bidirectional"))
      (node (ref "U4") (pin "19") (pinfunction "TX0_19") (pintype "bidirectional"))
    )
    (net (code "66") (name "USB_N") (class "Default")
      (node (ref "J2") (pin "D-") (pinfunction "D-_D-") (pintype "bidirectional"))
      (node (ref "U1") (pin "9") (pinfunction "REFI/RP11/CTED9/CN15/PGC2/D-/RB11_9") (pintype "bidirectional"))
    )
    (net (code "67") (name "USB_P") (class "Default")
      (node (ref "J2") (pin "D+") (pinfunction "D+_D+") (pintype "bidirectional"))
      (node (ref "U1") (pin "8") (pinfunction "RP10/CTED11/CN16/PGD2/D+/RB10_8") (pintype "bidirectional"))
    )
    (net (code "68") (name "VBAT") (class "Default")
      (node (ref "BAT+") (pin "TP") (pinfunction "TP_TP") (pintype "input"))
      (node (ref "C12") (pin "1") (pinfunction "1_1") (pintype "passive"))
      (node (ref "SJ4") (pin "1") (pinfunction "1_1") (pintype "passive"))
      (node (ref "U8") (pin "14") (pinfunction "VBAT1_14") (pintype "output"))
      (node (ref "U8") (pin "15") (pinfunction "VBAT2_15") (pintype "output"))
      (node (ref "U8") (pin "16") (pinfunction "VBAT3_16") (pintype "output"))
      (node (ref "U9") (pin "55") (pinfunction "VBAT_55") (pintype "power_in"))
      (node (ref "U9") (pin "56") (pinfunction "VBAT_56") (pintype "power_in"))
      (node (ref "U9") (pin "57") (pinfunction "VBAT_57") (pintype "power_in"))
    )
    (net (code "69") (name "V_USB") (class "Default")
      (node (ref "J2") (pin "VBUS") (pinfunction "VBUS_VBUS") (pintype "power_in"))
      (node (ref "LED1") (pin "A") (pinfunction "A_A") (pintype "passive"))
      (node (ref "LED2") (pin "A") (pinfunction "A_A") (pintype "passive"))
      (node (ref "R6") (pin "2") (pinfunction "2_2") (pintype "passive"))
      (node (ref "U8") (pin "17") (pinfunction "CE_17") (pintype "input"))
      (node (ref "U8") (pin "18") (pinfunction "IN1_18") (pintype "input"))
      (node (ref "U8") (pin "19") (pinfunction "IN2_19") (pintype "input"))
      (node (ref "U8") (pin "3") (pinfunction "SEL_3") (pintype "input"))
      (node (ref "U8") (pin "4") (pinfunction "PROG2_4") (pintype "input"))
      (node (ref "U8") (pin "9") (pinfunction "/TE_9") (pintype "input"))
    )
    (net (code "70") (name "WP") (class "Default")
      (node (ref "U1") (pin "42") (pinfunction "PMD6/CN24/VBUS/RB6_42") (pintype "bidirectional"))
      (node (ref "U5") (pin "5") (pinfunction "WP_5") (pintype "bidirectional"))
    )
    (net (code "71") (name "unconnected-(CON1-PadC4)") (class "Default")
      (node (ref "CON1") (pin "C4") (pinfunction "C4_C4") (pintype "bidirectional"))
    )
    (net (code "72") (name "unconnected-(CON1-PadC6)") (class "Default")
      (node (ref "CON1") (pin "C6") (pinfunction "C6_C6") (pintype "bidirectional"))
    )
    (net (code "73") (name "unconnected-(CON1-PadC8)") (class "Default")
      (node (ref "CON1") (pin "C8") (pinfunction "C8_C8") (pintype "bidirectional"))
    )
    (net (code "74") (name "unconnected-(J1-PadID)") (class "Default")
      (node (ref "J1") (pin "ID") (pinfunction "ID_ID") (pintype "bidirectional"))
    )
    (net (code "75") (name "unconnected-(J2-PadID)") (class "Default")
      (node (ref "J2") (pin "ID") (pinfunction "ID_ID") (pintype "bidirectional"))
    )
    (net (code "76") (name "unconnected-(SJ7-Pad2)") (class "Default")
      (node (ref "SJ7") (pin "2") (pinfunction "2_2") (pintype "passive"))
    )
    (net (code "77") (name "unconnected-(U1-AN10{slash}RP16{slash}PMBE1{slash}CN8{slash}RC0-Pad25)") (class "Default")
      (node (ref "U1") (pin "25") (pinfunction "AN10/RP16/PMBE1/CN8/RC0_25") (pintype "bidirectional"))
    )
    (net (code "78") (name "unconnected-(U1-CVREF+{slash}VREF+{slash}AN0{slash}C3INC{slash}RP5{slash}ASDA1{slash}CTED1{slash}CN2{slash}PMD7{slash}PGD3{slash}RA0-Pad19)") (class "Default")
      (node (ref "U1") (pin "19") (pinfunction "CVREF+/VREF+/AN0/C3INC/RP5/ASDA1/CTED1/CN2/PMD7/PGD3/RA0_19") (pintype "bidirectional"))
    )
    (net (code "79") (name "unconnected-(U1-CVREF-{slash}VREF-{slash}AN1{slash}C3IND{slash}RP6{slash}ASCL1{slash}CTED2{slash}CN3{slash}PGC3{slash}RA1-Pad20)") (class "Default")
      (node (ref "U1") (pin "20") (pinfunction "CVREF-/VREF-/AN1/C3IND/RP6/ASCL1/CTED2/CN3/PGC3/RA1_20") (pintype "bidirectional"))
    )
    (net (code "80") (name "unconnected-(U1-SOSCO{slash}SCLKI{slash}CN0{slash}RA4-Pad34)") (class "Default")
      (node (ref "U1") (pin "34") (pinfunction "SOSCO/SCLKI/CN0/RA4_34") (pintype "bidirectional"))
    )
    (net (code "81") (name "unconnected-(U1-TCK{slash}PMA7{slash}CN33{slash}RA7-Pad13)") (class "Default")
      (node (ref "U1") (pin "13") (pinfunction "TCK/PMA7/CN33/RA7_13") (pintype "bidirectional"))
    )
    (net (code "82") (name "unconnected-(U1-TDI{slash}PMA9{slash}CN35{slash}RA9-Pad35)") (class "Default")
      (node (ref "U1") (pin "35") (pinfunction "TDI/PMA9/CN35/RA9_35") (pintype "bidirectional"))
    )
    (net (code "83") (name "unconnected-(U1-TDO{slash}PMA8{slash}CN34{slash}RA8-Pad32)") (class "Default")
      (node (ref "U1") (pin "32") (pinfunction "TDO/PMA8/CN34/RA8_32") (pintype "bidirectional"))
    )
    (net (code "84") (name "unconnected-(U1-TMS{slash}PMA2{slash}PMALU{slash}CN36{slash}RA10-Pad12)") (class "Default")
      (node (ref "U1") (pin "12") (pinfunction "TMS/PMA2/PMALU/CN36/RA10_12") (pintype "bidirectional"))
    )
    (net (code "85") (name "unconnected-(U1-VBAT-Pad6)") (class "Default")
      (node (ref "U1") (pin "6") (pinfunction "VBAT_6") (pintype "bidirectional"))
    )
    (net (code "86") (name "unconnected-(U4-1PPS-Pad21)") (class "Default")
      (node (ref "U4") (pin "21") (pinfunction "1PPS_21") (pintype "bidirectional"))
    )
    (net (code "87") (name "unconnected-(U4-CLK-Pad18)") (class "Default")
      (node (ref "U4") (pin "18") (pinfunction "CLK_18") (pintype "bidirectional"))
    )
    (net (code "88") (name "unconnected-(U4-CS-Pad23)") (class "Default")
      (node (ref "U4") (pin "23") (pinfunction "CS_23") (pintype "bidirectional"))
    )
    (net (code "89") (name "unconnected-(U4-EX_ANT-Pad2)") (class "Default")
      (node (ref "U4") (pin "2") (pinfunction "EX_ANT_2") (pintype "bidirectional"))
    )
    (net (code "90") (name "unconnected-(U4-I2C_SCL-Pad14)") (class "Default")
      (node (ref "U4") (pin "14") (pinfunction "I2C_SCL_14") (pintype "bidirectional"))
    )
    (net (code "91") (name "unconnected-(U4-I2C_SDA-Pad13)") (class "Default")
      (node (ref "U4") (pin "13") (pinfunction "I2C_SDA_13") (pintype "bidirectional"))
    )
    (net (code "92") (name "unconnected-(U4-INT-Pad16)") (class "Default")
      (node (ref "U4") (pin "16") (pinfunction "INT_16") (pintype "bidirectional"))
    )
    (net (code "93") (name "unconnected-(U4-MISO-Pad15)") (class "Default")
      (node (ref "U4") (pin "15") (pinfunction "MISO_15") (pintype "bidirectional"))
    )
    (net (code "94") (name "unconnected-(U4-MOSI-Pad17)") (class "Default")
      (node (ref "U4") (pin "17") (pinfunction "MOSI_17") (pintype "bidirectional"))
    )
    (net (code "95") (name "unconnected-(U4-NRESET-Pad22)") (class "Default")
      (node (ref "U4") (pin "22") (pinfunction "NRESET_22") (pintype "bidirectional"))
    )
    (net (code "96") (name "unconnected-(U8-{slash}PG-Pad6)") (class "Default")
      (node (ref "U8") (pin "6") (pinfunction "/PG_6") (pintype "output"))
    )
    (net (code "97") (name "unconnected-(U9-ADC-Pad25)") (class "Default")
      (node (ref "U9") (pin "25") (pinfunction "ADC_25") (pintype "bidirectional"))
    )
    (net (code "98") (name "unconnected-(U9-DCD-Pad5)") (class "Default")
      (node (ref "U9") (pin "5") (pinfunction "DCD_5") (pintype "bidirectional"))
    )
    (net (code "99") (name "unconnected-(U9-DTR-Pad3)") (class "Default")
      (node (ref "U9") (pin "3") (pinfunction "DTR_3") (pintype "bidirectional"))
    )
    (net (code "100") (name "unconnected-(U9-GPIO0{slash}UART3_TXD-Pad50)") (class "Default")
      (node (ref "U9") (pin "50") (pinfunction "GPIO0/UART3_TXD_50") (pintype "bidirectional"))
    )
    (net (code "101") (name "unconnected-(U9-GPIO1{slash}UART3_RXD-Pad49)") (class "Default")
      (node (ref "U9") (pin "49") (pinfunction "GPIO1/UART3_RXD_49") (pintype "bidirectional"))
    )
    (net (code "102") (name "unconnected-(U9-GPIO2-Pad67)") (class "Default")
      (node (ref "U9") (pin "67") (pinfunction "GPIO2_67") (pintype "bidirectional"))
    )
    (net (code "103") (name "unconnected-(U9-GPIO3-Pad68)") (class "Default")
      (node (ref "U9") (pin "68") (pinfunction "GPIO3_68") (pintype "bidirectional"))
    )
    (net (code "104") (name "unconnected-(U9-GPIO4-Pad48)") (class "Default")
      (node (ref "U9") (pin "48") (pinfunction "GPIO4_48") (pintype "bidirectional"))
    )
    (net (code "105") (name "unconnected-(U9-I2C_SCL-Pad38)") (class "Default")
      (node (ref "U9") (pin "38") (pinfunction "I2C_SCL_38") (pintype "bidirectional"))
    )
    (net (code "106") (name "unconnected-(U9-I2C_SDA-Pad37)") (class "Default")
      (node (ref "U9") (pin "37") (pinfunction "I2C_SDA_37") (pintype "bidirectional"))
    )
    (net (code "107") (name "unconnected-(U9-NC-Pad19)") (class "Default")
      (node (ref "U9") (pin "19") (pinfunction "NC_19") (pintype "bidirectional"))
    )
    (net (code "108") (name "unconnected-(U9-NC-Pad20)") (class "Default")
      (node (ref "U9") (pin "20") (pinfunction "NC_20") (pintype "bidirectional"))
    )
    (net (code "109") (name "unconnected-(U9-NC-Pad21)") (class "Default")
      (node (ref "U9") (pin "21") (pinfunction "NC_21") (pintype "bidirectional"))
    )
    (net (code "110") (name "unconnected-(U9-NC-Pad22)") (class "Default")
      (node (ref "U9") (pin "22") (pinfunction "NC_22") (pintype "bidirectional"))
    )
    (net (code "111") (name "unconnected-(U9-NC-Pad26)") (class "Default")
      (node (ref "U9") (pin "26") (pinfunction "NC_26") (pintype "bidirectional"))
    )
    (net (code "112") (name "unconnected-(U9-NC-Pad35)") (class "Default")
      (node (ref "U9") (pin "35") (pinfunction "NC_35") (pintype "bidirectional"))
    )
    (net (code "113") (name "unconnected-(U9-NC-Pad36)") (class "Default")
      (node (ref "U9") (pin "36") (pinfunction "NC_36") (pintype "bidirectional"))
    )
    (net (code "114") (name "unconnected-(U9-NC-Pad40)") (class "Default")
      (node (ref "U9") (pin "40") (pinfunction "NC_40") (pintype "bidirectional"))
    )
    (net (code "115") (name "unconnected-(U9-NC-Pad41\\)") (class "Default")
      (node (ref "U9") (pin "41\\") (pinfunction "NC_41\\") (pintype "bidirectional"))
    )
    (net (code "116") (name "unconnected-(U9-NC-Pad42)") (class "Default")
      (node (ref "U9") (pin "42") (pinfunction "NC_42") (pintype "bidirectional"))
    )
    (net (code "117") (name "unconnected-(U9-NC-Pad43)") (class "Default")
      (node (ref "U9") (pin "43") (pinfunction "NC_43") (pintype "bidirectional"))
    )
    (net (code "118") (name "unconnected-(U9-NC-Pad44)") (class "Default")
      (node (ref "U9") (pin "44") (pinfunction "NC_44") (pintype "bidirectional"))
    )
    (net (code "119") (name "unconnected-(U9-NC-Pad47)") (class "Default")
      (node (ref "U9") (pin "47") (pinfunction "NC_47") (pintype "bidirectional"))
    )
    (net (code "120") (name "unconnected-(U9-NC-Pad51)") (class "Default")
      (node (ref "U9") (pin "51") (pinfunction "NC_51") (pintype "bidirectional"))
    )
    (net (code "121") (name "unconnected-(U9-PCM_CLK-Pad11)") (class "Default")
      (node (ref "U9") (pin "11") (pinfunction "PCM_CLK_11") (pintype "bidirectional"))
    )
    (net (code "122") (name "unconnected-(U9-PCM_DIN-Pad13)") (class "Default")
      (node (ref "U9") (pin "13") (pinfunction "PCM_DIN_13") (pintype "bidirectional"))
    )
    (net (code "123") (name "unconnected-(U9-PCM_DOUT-Pad14)") (class "Default")
      (node (ref "U9") (pin "14") (pinfunction "PCM_DOUT_14") (pintype "bidirectional"))
    )
    (net (code "124") (name "unconnected-(U9-PCM_SYNC-Pad12)") (class "Default")
      (node (ref "U9") (pin "12") (pinfunction "PCM_SYNC_12") (pintype "bidirectional"))
    )
    (net (code "125") (name "unconnected-(U9-RI-Pad4)") (class "Default")
      (node (ref "U9") (pin "4") (pinfunction "RI_4") (pintype "bidirectional"))
    )
    (net (code "126") (name "unconnected-(U9-SIM_DET-Pad34)") (class "Default")
      (node (ref "U9") (pin "34") (pinfunction "SIM_DET_34") (pintype "bidirectional"))
    )
  )
)
